# geiger.net
KiCad netlist of a schematic drawn in EAGLE
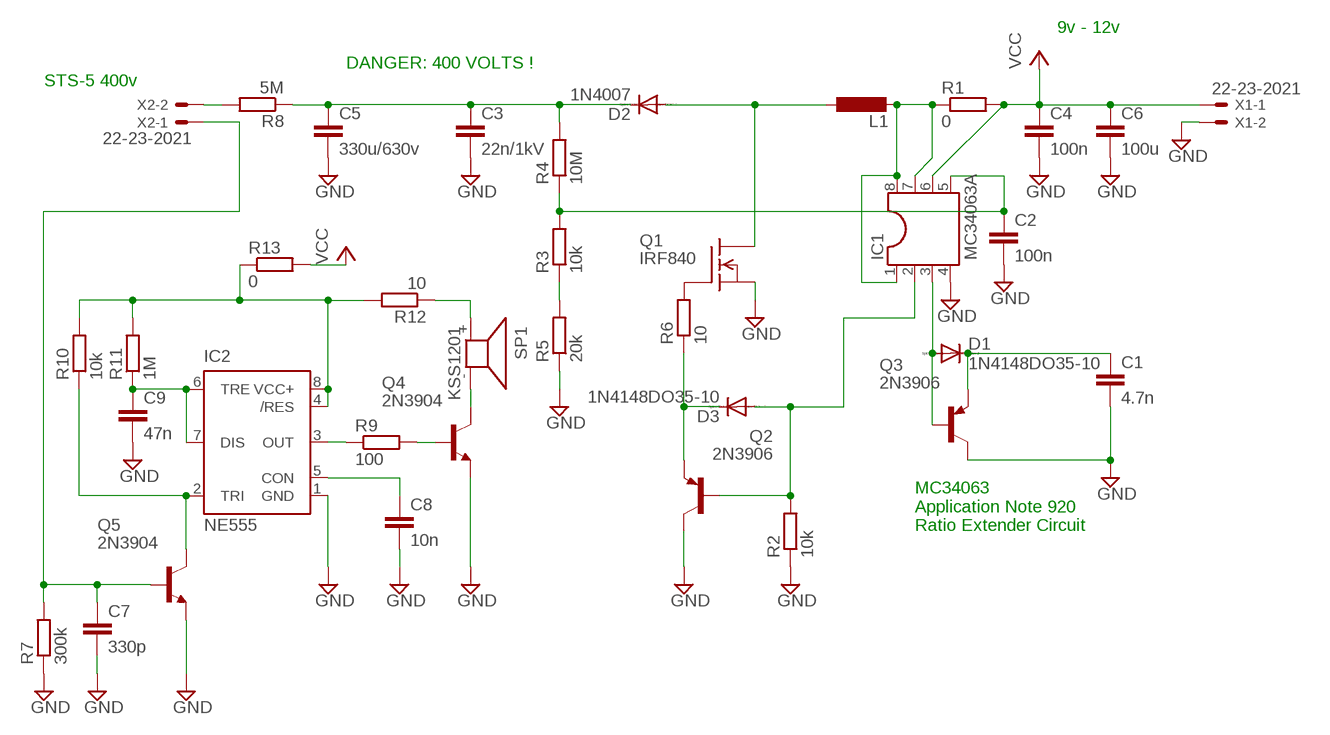
[diagram p0: schematic, sheet 1]

(export (version "E")
  (design (tool "Eeschema 10.0.6"))
  (components
    (comp (ref "C1")
      (value "4.7n")
      (footprint "eagle-import:C025-025X050")
      (libsource (lib "eagle-import") (part "C-EU025-025X050"))
    )
    (comp (ref "C2")
      (value "100n")
      (footprint "eagle-import:C025-025X050")
      (libsource (lib "eagle-import") (part "C-EU025-025X050"))
    )
    (comp (ref "C3")
      (value "22n/1kV")
      (footprint "eagle-import:C050-050X075")
      (libsource (lib "eagle-import") (part "C-EU050-050X075"))
    )
    (comp (ref "C4")
      (value "100n")
      (footprint "eagle-import:C025-025X050")
      (libsource (lib "eagle-import") (part "C-EU025-025X050"))
    )
    (comp (ref "C5")
      (value "330u/630v")
      (footprint "eagle-import:C050-050X075")
      (libsource (lib "eagle-import") (part "C-EU050-050X075"))
    )
    (comp (ref "C6")
      (value "100u")
      (footprint "eagle-import:C025-025X050")
      (libsource (lib "eagle-import") (part "C-EU025-025X050"))
    )
    (comp (ref "C7")
      (value "330p")
      (footprint "eagle-import:C025-025X050")
      (libsource (lib "eagle-import") (part "C-EU025-025X050"))
    )
    (comp (ref "C8")
      (value "10n")
      (footprint "eagle-import:C025-025X050")
      (libsource (lib "eagle-import") (part "C-EU025-025X050"))
    )
    (comp (ref "C9")
      (value "47n")
      (footprint "eagle-import:C025-025X050")
      (libsource (lib "eagle-import") (part "C-EU025-025X050"))
    )
    (comp (ref "D1")
      (value "1N4148DO35-10")
      (footprint "eagle-import:DO35-10")
      (libsource (lib "eagle-import") (part "1N4148DO35-10"))
    )
    (comp (ref "D2")
      (value "1N4007")
      (footprint "eagle-import:D-7.5")
      (libsource (lib "eagle-import") (part "DIODE-D-7.5"))
    )
    (comp (ref "D3")
      (value "1N4148DO35-10")
      (footprint "eagle-import:DO35-10")
      (libsource (lib "eagle-import") (part "1N4148DO35-10"))
    )
    (comp (ref "IC1")
      (value "MC34063A")
      (footprint "eagle-import:DIL08")
      (libsource (lib "eagle-import") (part "DIL8"))
    )
    (comp (ref "IC2")
      (value "NE555")
      (footprint "eagle-import:DIL-08")
      (fields (field (name "MF") "Arrow Electronics") (field (name "MPN") "NE555N"))
      (libsource (lib "eagle-import") (part "NE555"))
    )
    (comp (ref "L1")
      (value "L-EU0207/12")
      (footprint "eagle-import:0207_12")
      (libsource (lib "eagle-import") (part "L-EU0207/12"))
    )
    (comp (ref "Q1")
      (value "IRF840")
      (footprint "eagle-import:TO220")
      (libsource (lib "eagle-import") (part "IRF840"))
    )
    (comp (ref "Q2")
      (value "2N3906")
      (footprint "eagle-import:TO92")
      (libsource (lib "eagle-import") (part "2N3906"))
    )
    (comp (ref "Q3")
      (value "2N3906")
      (footprint "eagle-import:TO92")
      (libsource (lib "eagle-import") (part "2N3906"))
    )
    (comp (ref "Q4")
      (value "2N3904")
      (footprint "eagle-import:TO92")
      (libsource (lib "eagle-import") (part "2N3904"))
    )
    (comp (ref "Q5")
      (value "2N3904")
      (footprint "eagle-import:TO92")
      (libsource (lib "eagle-import") (part "2N3904"))
    )
    (comp (ref "R1")
      (value "0")
      (footprint "eagle-import:0204_7")
      (libsource (lib "eagle-import") (part "R-EU_0204/7"))
    )
    (comp (ref "R2")
      (value "10k")
      (footprint "eagle-import:0204_7")
      (libsource (lib "eagle-import") (part "R-EU_0204/7"))
    )
    (comp (ref "R3")
      (value "10k")
      (footprint "eagle-import:0204_7")
      (libsource (lib "eagle-import") (part "R-EU_0204/7"))
    )
    (comp (ref "R4")
      (value "10M")
      (footprint "eagle-import:0204_7")
      (libsource (lib "eagle-import") (part "R-EU_0204/7"))
    )
    (comp (ref "R5")
      (value "20k")
      (footprint "eagle-import:0204_7")
      (libsource (lib "eagle-import") (part "R-EU_0204/7"))
    )
    (comp (ref "R6")
      (value "10")
      (footprint "eagle-import:0204_7")
      (libsource (lib "eagle-import") (part "R-EU_0204/7"))
    )
    (comp (ref "R7")
      (value "300k")
      (footprint "eagle-import:0204_7")
      (libsource (lib "eagle-import") (part "R-EU_0204/7"))
    )
    (comp (ref "R8")
      (value "5M")
      (footprint "eagle-import:0204_7")
      (libsource (lib "eagle-import") (part "R-EU_0204/7"))
    )
    (comp (ref "R9")
      (value "100")
      (footprint "eagle-import:0204_7")
      (libsource (lib "eagle-import") (part "R-EU_0204/7"))
    )
    (comp (ref "R10")
      (value "10k")
      (footprint "eagle-import:0204_7")
      (libsource (lib "eagle-import") (part "R-EU_0204/7"))
    )
    (comp (ref "R11")
      (value "1M")
      (footprint "eagle-import:0204_7")
      (libsource (lib "eagle-import") (part "R-EU_0204/7"))
    )
    (comp (ref "R12")
      (value "10")
      (footprint "eagle-import:0204_7")
      (libsource (lib "eagle-import") (part "R-EU_0204/7"))
    )
    (comp (ref "R13")
      (value "0")
      (footprint "eagle-import:0204_7")
      (libsource (lib "eagle-import") (part "R-EU_0204/7"))
    )
    (comp (ref "SP1")
      (value "KSS1201")
      (footprint "eagle-import:KSS1201")
      (libsource (lib "eagle-import") (part "KSS1201"))
    )
    (comp (ref "X1")
      (value "22-23-2021")
      (footprint "eagle-import:22-23-2021")
      (fields (field (name "MF") "MOLEX"))
      (libsource (lib "eagle-import") (part "22-23-2021"))
    )
    (comp (ref "X2")
      (value "22-23-2021")
      (footprint "eagle-import:22-23-2021")
      (fields (field (name "MF") "MOLEX"))
      (libsource (lib "eagle-import") (part "22-23-2021"))
    )
  )
  (nets
    (net (code "1") (name "GND") (class "Default")
      (node (ref "C1") (pin "2") (pinfunction "2_2") (pintype "passive"))
      (node (ref "C2") (pin "2") (pinfunction "2_2") (pintype "passive"))
      (node (ref "C3") (pin "2") (pinfunction "2_2") (pintype "passive"))
      (node (ref "C4") (pin "2") (pinfunction "2_2") (pintype "passive"))
      (node (ref "C5") (pin "2") (pinfunction "2_2") (pintype "passive"))
      (node (ref "C6") (pin "2") (pinfunction "2_2") (pintype "passive"))
      (node (ref "C7") (pin "2") (pinfunction "2_2") (pintype "passive"))
      (node (ref "C8") (pin "2") (pinfunction "2_2") (pintype "passive"))
      (node (ref "C9") (pin "2") (pinfunction "2_2") (pintype "passive"))
      (node (ref "IC1") (pin "4") (pinfunction "4_4") (pintype "passive"))
      (node (ref "IC2") (pin "1") (pinfunction "GND_1") (pintype "power_in"))
      (node (ref "Q1") (pin "3") (pinfunction "S_3") (pintype "passive"))
      (node (ref "Q2") (pin "1") (pinfunction "C_1") (pintype "passive"))
      (node (ref "Q3") (pin "1") (pinfunction "C_1") (pintype "passive"))
      (node (ref "Q4") (pin "3") (pinfunction "E_3") (pintype "passive"))
      (node (ref "Q5") (pin "3") (pinfunction "E_3") (pintype "passive"))
      (node (ref "R2") (pin "1") (pinfunction "1_1") (pintype "passive"))
      (node (ref "R5") (pin "1") (pinfunction "1_1") (pintype "passive"))
      (node (ref "R7") (pin "1") (pinfunction "1_1") (pintype "passive"))
      (node (ref "X1") (pin "2") (pinfunction "S_2") (pintype "passive"))
    )
    (net (code "2") (name "Net-(C2-Pad1)") (class "Default")
      (node (ref "C2") (pin "1") (pinfunction "1_1") (pintype "passive"))
      (node (ref "IC1") (pin "5") (pinfunction "5_5") (pintype "passive"))
      (node (ref "R3") (pin "2") (pinfunction "2_2") (pintype "passive"))
      (node (ref "R4") (pin "1") (pinfunction "1_1") (pintype "passive"))
    )
    (net (code "3") (name "Net-(C3-Pad1)") (class "Default")
      (node (ref "C3") (pin "1") (pinfunction "1_1") (pintype "passive"))
      (node (ref "C5") (pin "1") (pinfunction "1_1") (pintype "passive"))
      (node (ref "D2") (pin "C") (pinfunction "C_C") (pintype "passive"))
      (node (ref "R4") (pin "2") (pinfunction "2_2") (pintype "passive"))
      (node (ref "R8") (pin "1") (pinfunction "1_1") (pintype "passive"))
    )
    (net (code "4") (name "Net-(IC1-Pad1)") (class "Default")
      (node (ref "IC1") (pin "1") (pinfunction "1_1") (pintype "passive"))
      (node (ref "IC1") (pin "7") (pinfunction "7_7") (pintype "passive"))
      (node (ref "IC1") (pin "8") (pinfunction "8_8") (pintype "passive"))
      (node (ref "L1") (pin "2") (pinfunction "2_2") (pintype "passive"))
      (node (ref "R1") (pin "1") (pinfunction "1_1") (pintype "passive"))
    )
    (net (code "5") (name "Net-(IC2-CON)") (class "Default")
      (node (ref "C8") (pin "1") (pinfunction "1_1") (pintype "passive"))
      (node (ref "IC2") (pin "5") (pinfunction "CON_5") (pintype "input"))
    )
    (net (code "6") (name "Net-(IC2-DIS)") (class "Default")
      (node (ref "C9") (pin "1") (pinfunction "1_1") (pintype "passive"))
      (node (ref "IC2") (pin "6") (pinfunction "TRE_6") (pintype "input"))
      (node (ref "IC2") (pin "7") (pinfunction "DIS_7") (pintype "input"))
      (node (ref "R11") (pin "1") (pinfunction "1_1") (pintype "passive"))
    )
    (net (code "7") (name "Net-(IC2-OUT)") (class "Default")
      (node (ref "IC2") (pin "3") (pinfunction "OUT_3") (pintype "output"))
      (node (ref "R9") (pin "1") (pinfunction "1_1") (pintype "passive"))
    )
    (net (code "8") (name "Net-(IC2-TRI)") (class "Default")
      (node (ref "IC2") (pin "2") (pinfunction "TRI_2") (pintype "input"))
      (node (ref "Q5") (pin "1") (pinfunction "C_1") (pintype "passive"))
      (node (ref "R10") (pin "1") (pinfunction "1_1") (pintype "passive"))
    )
    (net (code "9") (name "Net-(IC2-VCC+)") (class "Default")
      (node (ref "IC2") (pin "4") (pinfunction "/RES_4") (pintype "input"))
      (node (ref "IC2") (pin "8") (pinfunction "VCC+_8") (pintype "power_in"))
      (node (ref "R10") (pin "2") (pinfunction "2_2") (pintype "passive"))
      (node (ref "R11") (pin "2") (pinfunction "2_2") (pintype "passive"))
      (node (ref "R12") (pin "2") (pinfunction "2_2") (pintype "passive"))
      (node (ref "R13") (pin "1") (pinfunction "1_1") (pintype "passive"))
    )
    (net (code "10") (name "Net-(Q1-D)") (class "Default")
      (node (ref "D2") (pin "A") (pinfunction "A_A") (pintype "passive"))
      (node (ref "L1") (pin "1") (pinfunction "1_1") (pintype "passive"))
      (node (ref "Q1") (pin "2") (pinfunction "D_2") (pintype "passive"))
    )
    (net (code "11") (name "Net-(Q1-G)") (class "Default")
      (node (ref "Q1") (pin "1") (pinfunction "G_1") (pintype "passive"))
      (node (ref "R6") (pin "2") (pinfunction "2_2") (pintype "passive"))
    )
    (net (code "12") (name "Net-(Q2-B)") (class "Default")
      (node (ref "D3") (pin "A") (pinfunction "A_A") (pintype "passive"))
      (node (ref "IC1") (pin "2") (pinfunction "2_2") (pintype "passive"))
      (node (ref "Q2") (pin "2") (pinfunction "B_2") (pintype "passive"))
      (node (ref "R2") (pin "2") (pinfunction "2_2") (pintype "passive"))
    )
    (net (code "13") (name "Net-(Q2-E)") (class "Default")
      (node (ref "D3") (pin "C") (pinfunction "C_C") (pintype "passive"))
      (node (ref "Q2") (pin "3") (pinfunction "E_3") (pintype "passive"))
      (node (ref "R6") (pin "1") (pinfunction "1_1") (pintype "passive"))
    )
    (net (code "14") (name "Net-(Q3-B)") (class "Default")
      (node (ref "D1") (pin "A") (pinfunction "A_A") (pintype "passive"))
      (node (ref "IC1") (pin "3") (pinfunction "3_3") (pintype "passive"))
      (node (ref "Q3") (pin "2") (pinfunction "B_2") (pintype "passive"))
    )
    (net (code "15") (name "Net-(Q3-E)") (class "Default")
      (node (ref "C1") (pin "1") (pinfunction "1_1") (pintype "passive"))
      (node (ref "D1") (pin "C") (pinfunction "C_C") (pintype "passive"))
      (node (ref "Q3") (pin "3") (pinfunction "E_3") (pintype "passive"))
    )
    (net (code "16") (name "Net-(Q4-B)") (class "Default")
      (node (ref "Q4") (pin "2") (pinfunction "B_2") (pintype "passive"))
      (node (ref "R9") (pin "2") (pinfunction "2_2") (pintype "passive"))
    )
    (net (code "17") (name "Net-(Q4-C)") (class "Default")
      (node (ref "Q4") (pin "1") (pinfunction "C_1") (pintype "passive"))
      (node (ref "SP1") (pin "-") (pinfunction "2_-") (pintype "passive"))
    )
    (net (code "18") (name "Net-(Q5-B)") (class "Default")
      (node (ref "C7") (pin "1") (pinfunction "1_1") (pintype "passive"))
      (node (ref "Q5") (pin "2") (pinfunction "B_2") (pintype "passive"))
      (node (ref "R7") (pin "2") (pinfunction "2_2") (pintype "passive"))
      (node (ref "X2") (pin "1") (pinfunction "S_1") (pintype "passive"))
    )
    (net (code "19") (name "Net-(R3-Pad1)") (class "Default")
      (node (ref "R3") (pin "1") (pinfunction "1_1") (pintype "passive"))
      (node (ref "R5") (pin "2") (pinfunction "2_2") (pintype "passive"))
    )
    (net (code "20") (name "Net-(SP1-1)") (class "Default")
      (node (ref "R12") (pin "1") (pinfunction "1_1") (pintype "passive"))
      (node (ref "SP1") (pin "+") (pinfunction "1_+") (pintype "passive"))
    )
    (net (code "21") (name "Net-(X2B-S)") (class "Default")
      (node (ref "R8") (pin "2") (pinfunction "2_2") (pintype "passive"))
      (node (ref "X2") (pin "2") (pinfunction "S_2") (pintype "passive"))
    )
    (net (code "22") (name "VCC") (class "Default")
      (node (ref "C4") (pin "1") (pinfunction "1_1") (pintype "passive"))
      (node (ref "C6") (pin "1") (pinfunction "1_1") (pintype "passive"))
      (node (ref "IC1") (pin "6") (pinfunction "6_6") (pintype "passive"))
      (node (ref "R1") (pin "2") (pinfunction "2_2") (pintype "passive"))
      (node (ref "R13") (pin "2") (pinfunction "2_2") (pintype "passive"))
      (node (ref "X1") (pin "1") (pinfunction "S_1") (pintype "passive"))
    )
  )
)
